# WaterSensor-V01-Build015.net
KiCad netlist of a schematic drawn in EAGLE
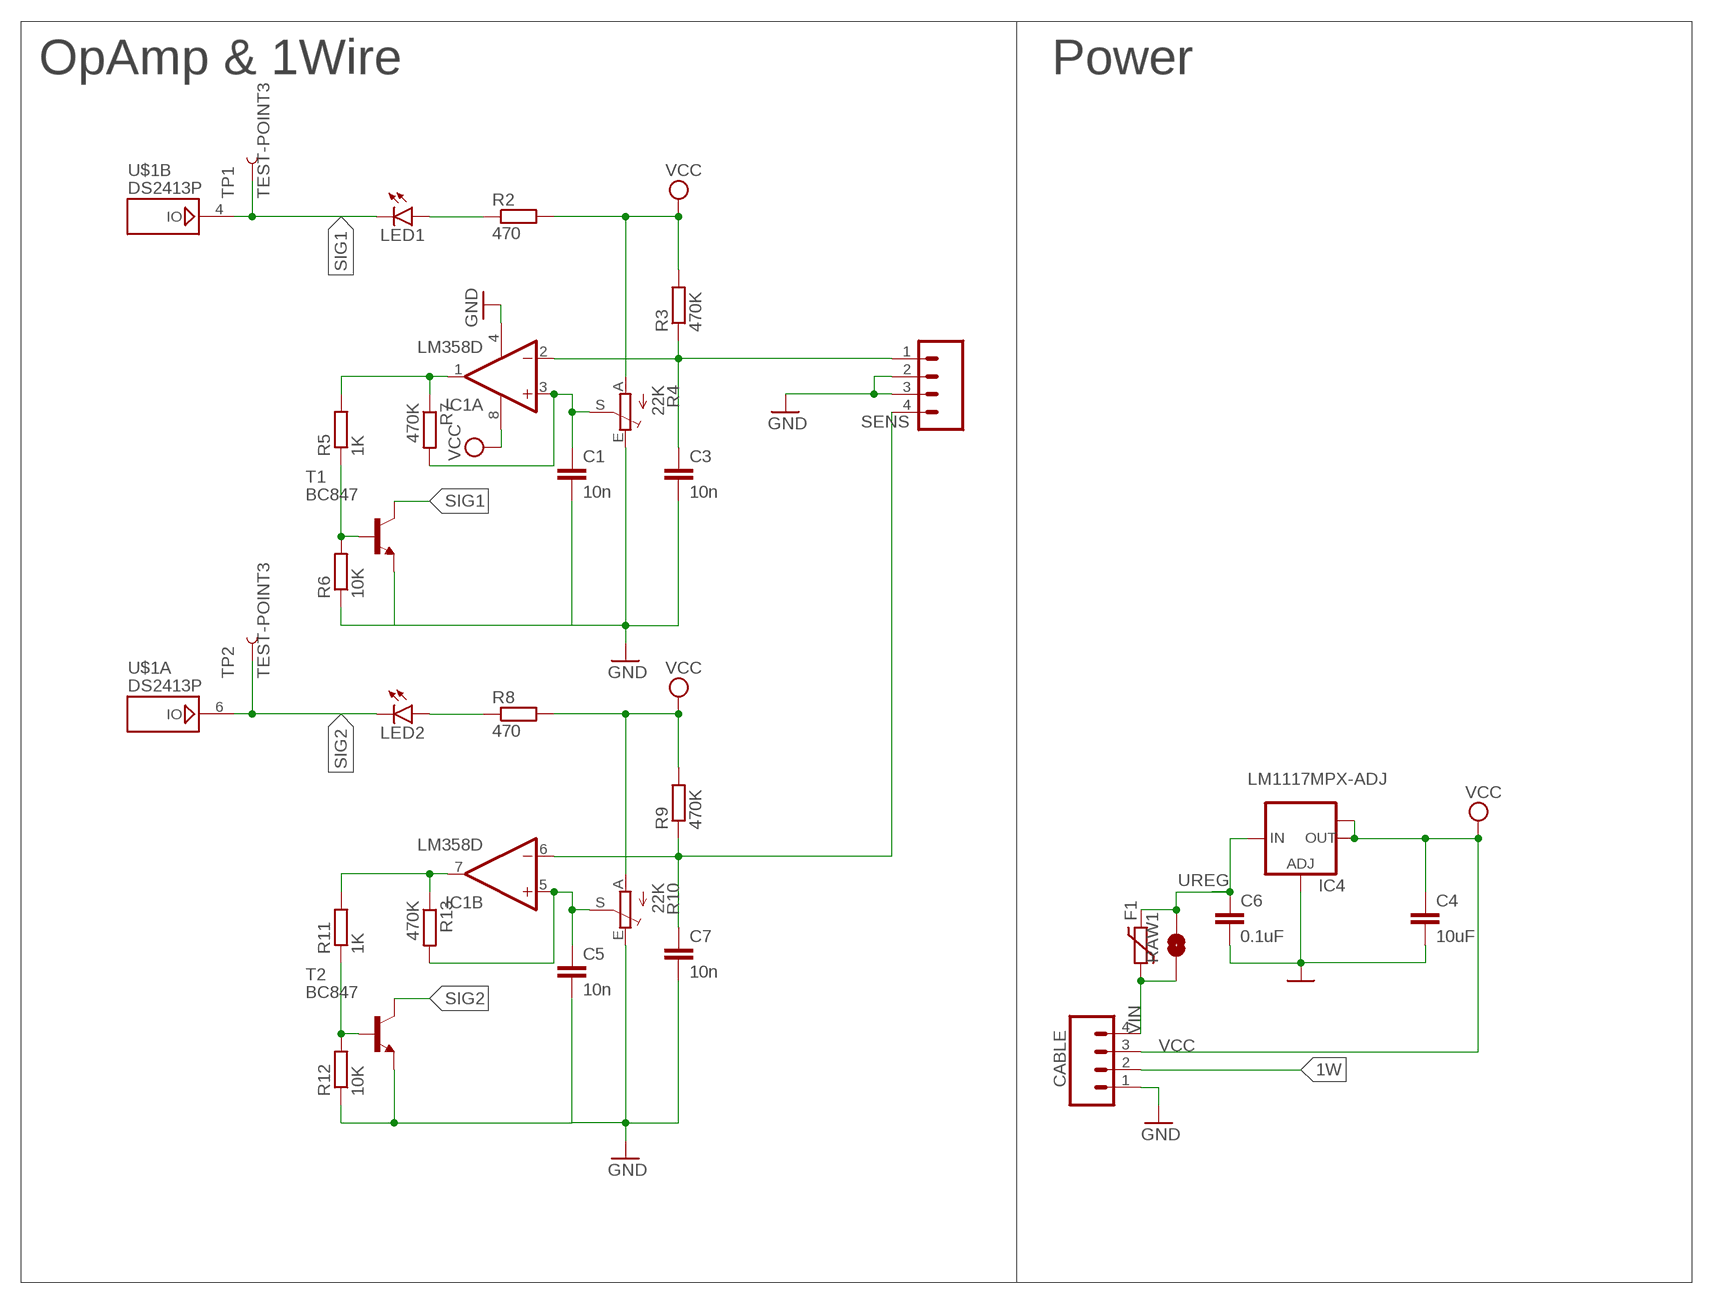
[diagram p0: schematic, sheet 1]

(export (version "E")
  (design (tool "Eeschema 10.0.6"))
  (components
    (comp (ref "C1")
      (value "10n")
      (footprint "eagle-import:C0805K")
      (libsource (lib "eagle-import") (part "rcl_334_C-EUC0805K"))
    )
    (comp (ref "C3")
      (value "10n")
      (footprint "eagle-import:C0805K")
      (libsource (lib "eagle-import") (part "rcl_334_C-EUC0805K"))
    )
    (comp (ref "C4")
      (value "10uF")
      (footprint "eagle-import:C1210")
      (libsource (lib "eagle-import") (part "C-EUC1210"))
    )
    (comp (ref "C5")
      (value "10n")
      (footprint "eagle-import:C0805K")
      (libsource (lib "eagle-import") (part "rcl_334_C-EUC0805K"))
    )
    (comp (ref "C6")
      (value "0.1uF")
      (footprint "eagle-import:C1206")
      (libsource (lib "eagle-import") (part "C-EUC1206"))
    )
    (comp (ref "C7")
      (value "10n")
      (footprint "eagle-import:C0805K")
      (libsource (lib "eagle-import") (part "rcl_334_C-EUC0805K"))
    )
    (comp (ref "CABLE")
      (value "CONN_04LONGPADS")
      (footprint "eagle-import:1X04_LONGPADS")
      (libsource (lib "eagle-import") (part "CONN_04LONGPADS"))
    )
    (comp (ref "F1")
      (value "1812L")
      (footprint "eagle-import:1812L")
      (libsource (lib "eagle-import") (part "1812L"))
    )
    (comp (ref "IC1")
      (value "LM358D")
      (footprint "eagle-import:SO08")
      (libsource (lib "eagle-import") (part "LM358D"))
    )
    (comp (ref "IC4")
      (value "LM1117MPX-ADJ")
      (footprint "eagle-import:SOT223")
      (libsource (lib "eagle-import") (part "LM1117MPX-ADJ"))
    )
    (comp (ref "LED1")
      (value "LEDCHIP-LED0805")
      (footprint "eagle-import:CHIP-LED0805")
      (libsource (lib "eagle-import") (part "LEDCHIP-LED0805"))
    )
    (comp (ref "LED2")
      (value "LEDCHIP-LED0805")
      (footprint "eagle-import:CHIP-LED0805")
      (libsource (lib "eagle-import") (part "LEDCHIP-LED0805"))
    )
    (comp (ref "R2")
      (value "470")
      (footprint "eagle-import:R0805W")
      (libsource (lib "eagle-import") (part "R-EU_R0805W"))
    )
    (comp (ref "R3")
      (value "470K")
      (footprint "eagle-import:R0805W")
      (libsource (lib "eagle-import") (part "R-EU_R0805W"))
    )
    (comp (ref "R4")
      (value "22K")
      (footprint "eagle-import:CA6V")
      (libsource (lib "eagle-import") (part "TRIM_EU-CA6V"))
    )
    (comp (ref "R5")
      (value "1K")
      (footprint "eagle-import:R0805W")
      (libsource (lib "eagle-import") (part "R-EU_R0805W"))
    )
    (comp (ref "R6")
      (value "10K")
      (footprint "eagle-import:R0805W")
      (libsource (lib "eagle-import") (part "R-EU_R0805W"))
    )
    (comp (ref "R7")
      (value "470K")
      (footprint "eagle-import:R0805W")
      (libsource (lib "eagle-import") (part "R-EU_R0805W"))
    )
    (comp (ref "R8")
      (value "470")
      (footprint "eagle-import:R0805W")
      (libsource (lib "eagle-import") (part "R-EU_R0805W"))
    )
    (comp (ref "R9")
      (value "470K")
      (footprint "eagle-import:R0805W")
      (libsource (lib "eagle-import") (part "R-EU_R0805W"))
    )
    (comp (ref "R10")
      (value "22K")
      (footprint "eagle-import:CA6V")
      (libsource (lib "eagle-import") (part "TRIM_EU-CA6V"))
    )
    (comp (ref "R11")
      (value "1K")
      (footprint "eagle-import:R0805W")
      (libsource (lib "eagle-import") (part "R-EU_R0805W"))
    )
    (comp (ref "R12")
      (value "10K")
      (footprint "eagle-import:R0805W")
      (libsource (lib "eagle-import") (part "R-EU_R0805W"))
    )
    (comp (ref "R13")
      (value "470K")
      (footprint "eagle-import:R0805W")
      (libsource (lib "eagle-import") (part "R-EU_R0805W"))
    )
    (comp (ref "RAW1")
      (value "JUMPER-SMT_2_NO_SILK")
      (footprint "eagle-import:SMT-JUMPER_2_NO_SILK")
      (libsource (lib "eagle-import") (part "JUMPER-SMT_2_NO_SILK"))
    )
    (comp (ref "SENS")
      (value "CONN_04LONGPADS")
      (footprint "eagle-import:1X04_LONGPADS")
      (libsource (lib "eagle-import") (part "CONN_04LONGPADS"))
    )
    (comp (ref "T1")
      (value "BC847")
      (footprint "eagle-import:SOT23")
      (libsource (lib "eagle-import") (part "BC847"))
    )
    (comp (ref "T2")
      (value "BC847")
      (footprint "eagle-import:SOT23")
      (libsource (lib "eagle-import") (part "BC847"))
    )
    (comp (ref "TP1")
      (value "TEST-POINT3")
      (footprint "eagle-import:PAD.03X.03")
      (libsource (lib "eagle-import") (part "TEST-POINT3"))
    )
    (comp (ref "TP2")
      (value "TEST-POINT3")
      (footprint "eagle-import:PAD.03X.03")
      (libsource (lib "eagle-import") (part "TEST-POINT3"))
    )
    (comp (ref "U$1")
      (value "DS2413P")
      (footprint "eagle-import:TSOC6")
      (libsource (lib "eagle-import") (part "DS2413P"))
    )
  )
  (nets
    (net (code "1") (name "/UREG") (class "Default")
      (node (ref "C6") (pin "1") (pinfunction "1_1") (pintype "passive"))
      (node (ref "F1") (pin "P$1") (pinfunction "1_P$1") (pintype "passive"))
      (node (ref "IC4") (pin "3") (pinfunction "IN_3") (pintype "input"))
      (node (ref "RAW1") (pin "2") (pinfunction "2_2") (pintype "passive"))
    )
    (net (code "2") (name "/VIN") (class "Default")
      (node (ref "CABLE") (pin "4") (pinfunction "4_4") (pintype "passive"))
      (node (ref "F1") (pin "P$2") (pinfunction "2_P$2") (pintype "passive"))
      (node (ref "RAW1") (pin "1") (pinfunction "1_1") (pintype "passive"))
    )
    (net (code "3") (name "1W") (class "Default")
      (node (ref "CABLE") (pin "2") (pinfunction "2_2") (pintype "passive"))
    )
    (net (code "4") (name "GND") (class "Default")
      (node (ref "C1") (pin "2") (pinfunction "2_2") (pintype "passive"))
      (node (ref "C3") (pin "2") (pinfunction "2_2") (pintype "passive"))
      (node (ref "C4") (pin "2") (pinfunction "2_2") (pintype "passive"))
      (node (ref "C5") (pin "2") (pinfunction "2_2") (pintype "passive"))
      (node (ref "C6") (pin "2") (pinfunction "2_2") (pintype "passive"))
      (node (ref "C7") (pin "2") (pinfunction "2_2") (pintype "passive"))
      (node (ref "CABLE") (pin "1") (pinfunction "1_1") (pintype "passive"))
      (node (ref "IC1") (pin "4") (pinfunction "V-_4") (pintype "power_in"))
      (node (ref "IC4") (pin "1") (pinfunction "ADJ_1") (pintype "input"))
      (node (ref "R10") (pin "E") (pinfunction "E_E") (pintype "passive"))
      (node (ref "R12") (pin "1") (pinfunction "1_1") (pintype "passive"))
      (node (ref "R4") (pin "E") (pinfunction "E_E") (pintype "passive"))
      (node (ref "R6") (pin "1") (pinfunction "1_1") (pintype "passive"))
      (node (ref "SENS") (pin "2") (pinfunction "2_2") (pintype "passive"))
      (node (ref "SENS") (pin "3") (pinfunction "3_3") (pintype "passive"))
      (node (ref "T1") (pin "2") (pinfunction "E_2") (pintype "passive"))
      (node (ref "T2") (pin "2") (pinfunction "E_2") (pintype "passive"))
    )
    (net (code "5") (name "Net-(IC1A-+IN)") (class "Default")
      (node (ref "C1") (pin "1") (pinfunction "1_1") (pintype "passive"))
      (node (ref "IC1") (pin "3") (pinfunction "+IN_3") (pintype "input"))
      (node (ref "R4") (pin "S") (pinfunction "S_S") (pintype "passive"))
      (node (ref "R7") (pin "2") (pinfunction "2_2") (pintype "passive"))
    )
    (net (code "6") (name "Net-(IC1A--IN)") (class "Default")
      (node (ref "C3") (pin "1") (pinfunction "1_1") (pintype "passive"))
      (node (ref "IC1") (pin "2") (pinfunction "-IN_2") (pintype "input"))
      (node (ref "R3") (pin "1") (pinfunction "1_1") (pintype "passive"))
      (node (ref "SENS") (pin "1") (pinfunction "1_1") (pintype "passive"))
    )
    (net (code "7") (name "Net-(IC1A-OUT)") (class "Default")
      (node (ref "IC1") (pin "1") (pinfunction "OUT_1") (pintype "output"))
      (node (ref "R5") (pin "2") (pinfunction "2_2") (pintype "passive"))
      (node (ref "R7") (pin "1") (pinfunction "1_1") (pintype "passive"))
    )
    (net (code "8") (name "Net-(IC1B-+IN)") (class "Default")
      (node (ref "C5") (pin "1") (pinfunction "1_1") (pintype "passive"))
      (node (ref "IC1") (pin "5") (pinfunction "+IN_5") (pintype "input"))
      (node (ref "R10") (pin "S") (pinfunction "S_S") (pintype "passive"))
      (node (ref "R13") (pin "2") (pinfunction "2_2") (pintype "passive"))
    )
    (net (code "9") (name "Net-(IC1B--IN)") (class "Default")
      (node (ref "C7") (pin "1") (pinfunction "1_1") (pintype "passive"))
      (node (ref "IC1") (pin "6") (pinfunction "-IN_6") (pintype "input"))
      (node (ref "R9") (pin "1") (pinfunction "1_1") (pintype "passive"))
      (node (ref "SENS") (pin "4") (pinfunction "4_4") (pintype "passive"))
    )
    (net (code "10") (name "Net-(IC1B-OUT)") (class "Default")
      (node (ref "IC1") (pin "7") (pinfunction "OUT_7") (pintype "output"))
      (node (ref "R11") (pin "2") (pinfunction "2_2") (pintype "passive"))
      (node (ref "R13") (pin "1") (pinfunction "1_1") (pintype "passive"))
    )
    (net (code "11") (name "Net-(LED1-PadA)") (class "Default")
      (node (ref "LED1") (pin "A") (pinfunction "A_A") (pintype "passive"))
      (node (ref "R2") (pin "1") (pinfunction "1_1") (pintype "passive"))
    )
    (net (code "12") (name "Net-(LED2-PadA)") (class "Default")
      (node (ref "LED2") (pin "A") (pinfunction "A_A") (pintype "passive"))
      (node (ref "R8") (pin "1") (pinfunction "1_1") (pintype "passive"))
    )
    (net (code "13") (name "Net-(T1-B)") (class "Default")
      (node (ref "R5") (pin "1") (pinfunction "1_1") (pintype "passive"))
      (node (ref "R6") (pin "2") (pinfunction "2_2") (pintype "passive"))
      (node (ref "T1") (pin "1") (pinfunction "B_1") (pintype "passive"))
    )
    (net (code "14") (name "Net-(T2-B)") (class "Default")
      (node (ref "R11") (pin "1") (pinfunction "1_1") (pintype "passive"))
      (node (ref "R12") (pin "2") (pinfunction "2_2") (pintype "passive"))
      (node (ref "T2") (pin "1") (pinfunction "B_1") (pintype "passive"))
    )
    (net (code "15") (name "SIG1") (class "Default")
      (node (ref "LED1") (pin "C") (pinfunction "C_C") (pintype "passive"))
      (node (ref "T1") (pin "3") (pinfunction "C_3") (pintype "passive"))
      (node (ref "TP1") (pin "P$1") (pinfunction "1_P$1") (pintype "bidirectional"))
      (node (ref "U$1") (pin "4") (pinfunction "IO_4") (pintype "open_collector"))
    )
    (net (code "16") (name "SIG2") (class "Default")
      (node (ref "LED2") (pin "C") (pinfunction "C_C") (pintype "passive"))
      (node (ref "T2") (pin "3") (pinfunction "C_3") (pintype "passive"))
      (node (ref "TP2") (pin "P$1") (pinfunction "1_P$1") (pintype "bidirectional"))
      (node (ref "U$1") (pin "6") (pinfunction "IO_6") (pintype "open_collector"))
    )
    (net (code "17") (name "VCC") (class "Default")
      (node (ref "C4") (pin "1") (pinfunction "1_1") (pintype "passive"))
      (node (ref "CABLE") (pin "3") (pinfunction "3_3") (pintype "passive"))
      (node (ref "IC1") (pin "8") (pinfunction "V+_8") (pintype "power_in"))
      (node (ref "IC4") (pin "2") (pinfunction "OUT_2") (pintype "passive"))
      (node (ref "IC4") (pin "TAB") (pinfunction "OUT1_TAB") (pintype "passive"))
      (node (ref "R10") (pin "A") (pinfunction "A_A") (pintype "passive"))
      (node (ref "R2") (pin "2") (pinfunction "2_2") (pintype "passive"))
      (node (ref "R3") (pin "2") (pinfunction "2_2") (pintype "passive"))
      (node (ref "R4") (pin "A") (pinfunction "A_A") (pintype "passive"))
      (node (ref "R8") (pin "2") (pinfunction "2_2") (pintype "passive"))
      (node (ref "R9") (pin "2") (pinfunction "2_2") (pintype "passive"))
    )
  )
)
